# ESP32-Proto2-Layout-D1.net
KiCad netlist of a schematic drawn in EAGLE
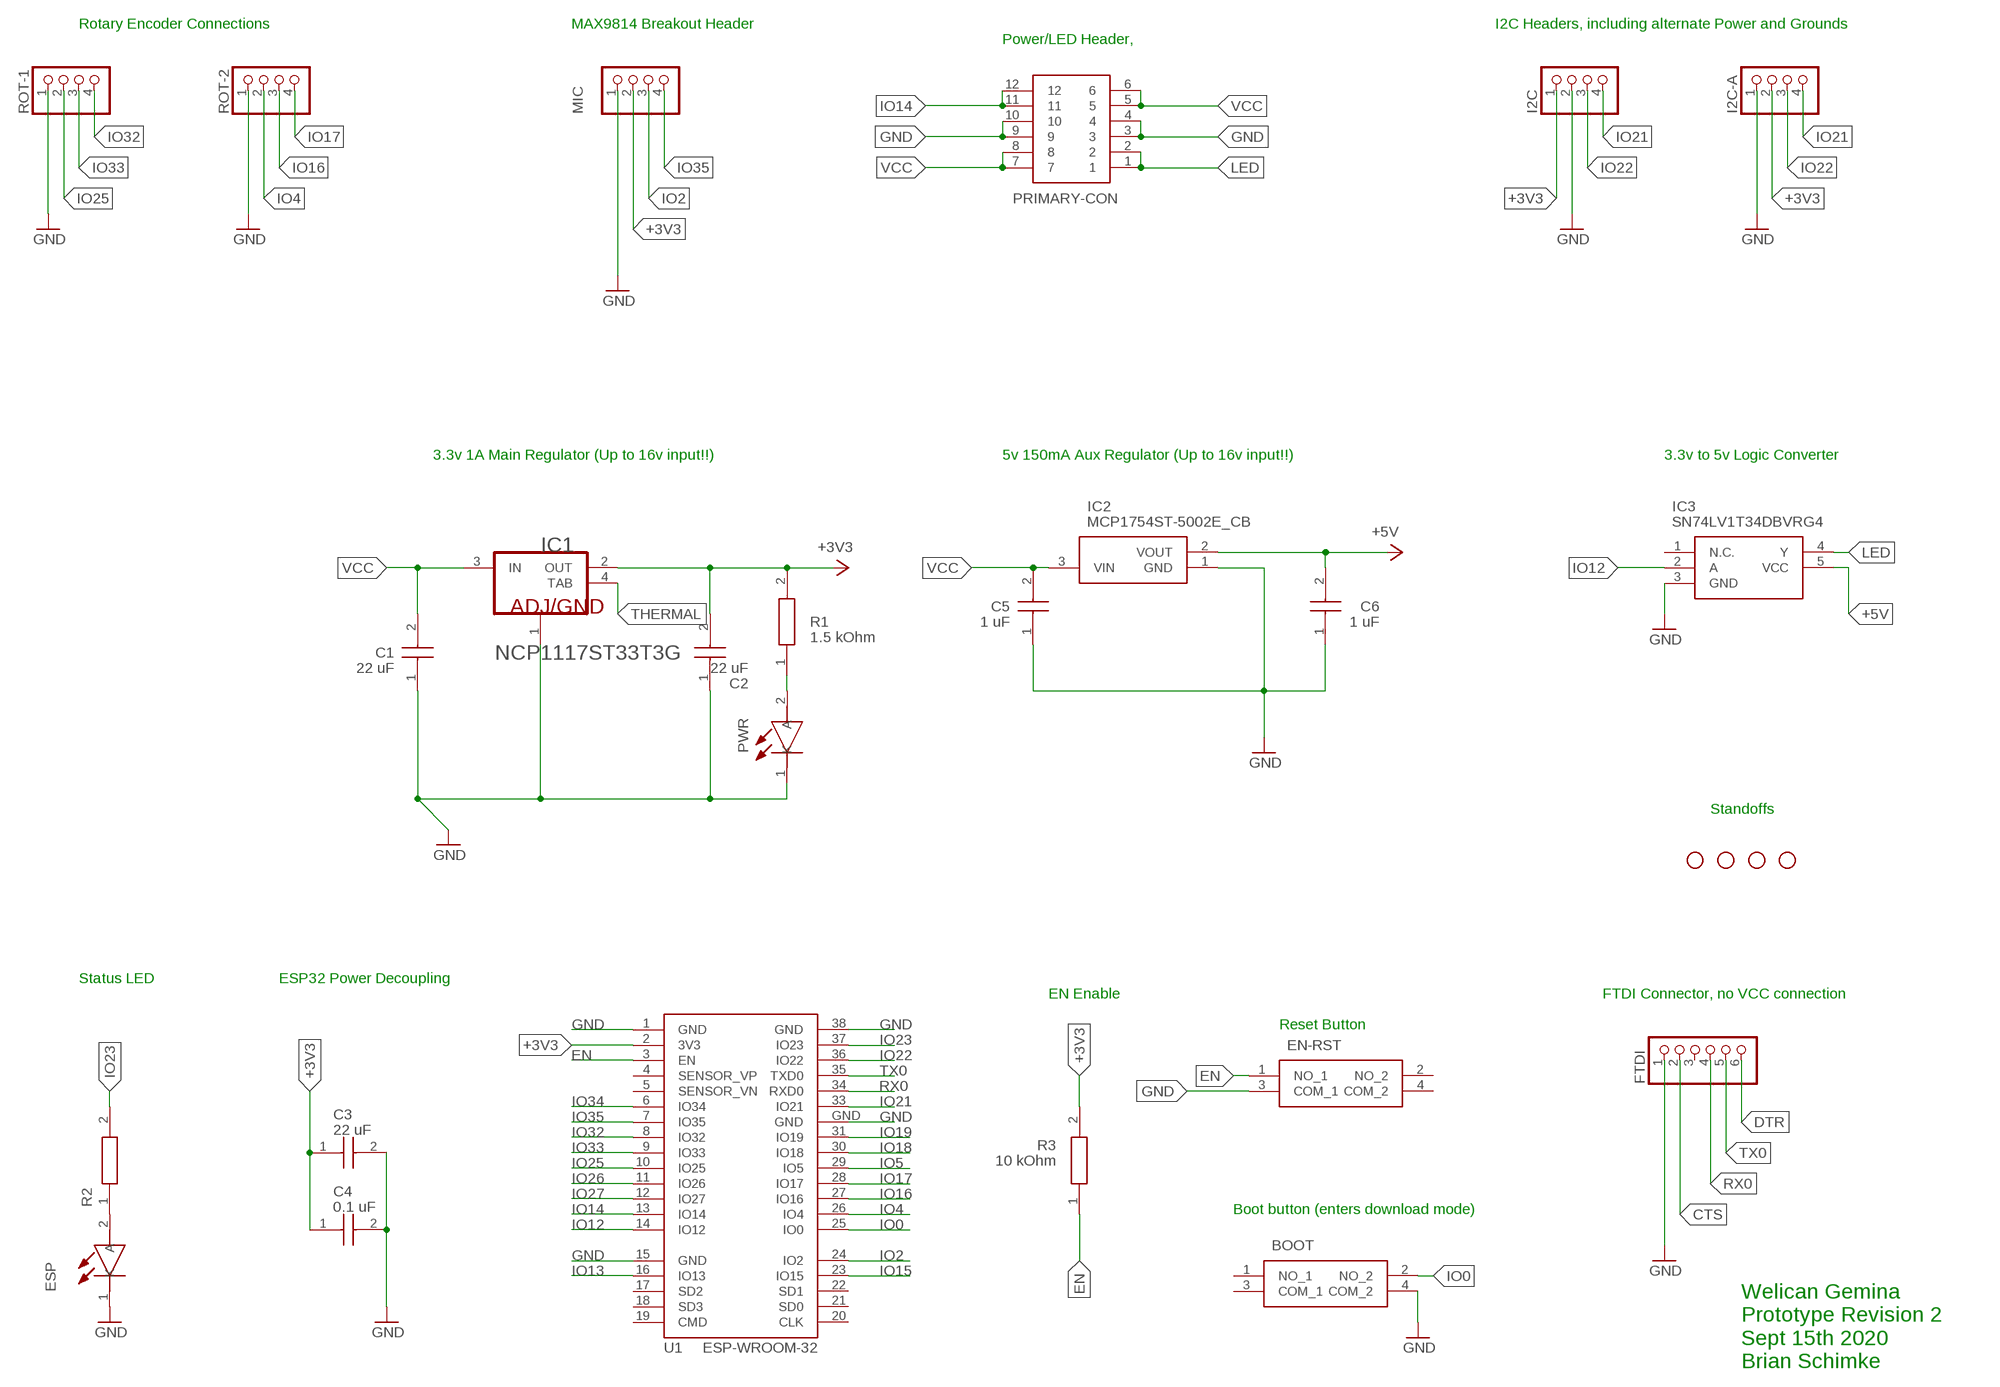
[diagram p0: schematic, sheet 1]

(export (version "E")
  (design (tool "Eeschema 10.0.6"))
  (components
    (comp (ref "BOOT")
      (value "PTS647SK70SMTR2LFS")
      (footprint "eagle-import:PTS647SK70SMTR2LFS")
      (fields (field (name "MOUSER_PART_NUMBER") "611-PTS647SK70SMTR2L"))
      (libsource (lib "eagle-import") (part "PTS647SK70SMTR2LFS"))
    )
    (comp (ref "C1")
      (value "22 uF")
      (footprint "eagle-import:CAPC3216X180N")
      (fields
        (field (name "MANUFACTURER_PART_NUMBER") "C1206C226M4PACTU")
        (field (name "MOUSER_PART_NUMBER") "80-C1206C226M4P")
      )
      (libsource (lib "eagle-import") (part "C1206C226M4PACTU"))
    )
    (comp (ref "C2")
      (value "22 uF")
      (footprint "eagle-import:CAPC3216X180N")
      (fields
        (field (name "MANUFACTURER_PART_NUMBER") "C1206C226M4PACTU")
        (field (name "MOUSER_PART_NUMBER") "80-C1206C226M4P")
      )
      (libsource (lib "eagle-import") (part "C1206C226M4PACTU"))
    )
    (comp (ref "C3")
      (value "22 uF")
      (footprint "eagle-import:CAPC3216X180N")
      (fields
        (field (name "MANUFACTURER_PART_NUMBER") "C1206C226M4PACTU")
        (field (name "MOUSER_PART_NUMBER") "80-C1206C226M4P")
      )
      (libsource (lib "eagle-import") (part "C1206C226M4PACTU"))
    )
    (comp (ref "C4")
      (value "0.1 uF")
      (footprint "eagle-import:CAPC3216X180N")
      (fields
        (field (name "MANUFACTURER_PART_NUMBER") "C1206C226M4PACTU")
        (field (name "MOUSER_PART_NUMBER") "80-C1206C226M4P")
      )
      (libsource (lib "eagle-import") (part "C1206C226M4PACTU"))
    )
    (comp (ref "C5")
      (value "1 uF")
      (footprint "eagle-import:CAPC3216X180N")
      (fields
        (field (name "MANUFACTURER_PART_NUMBER") "C1206C226M4PACTU")
        (field (name "MOUSER_PART_NUMBER") "80-C1206C226M4P")
      )
      (libsource (lib "eagle-import") (part "C1206C226M4PACTU"))
    )
    (comp (ref "C6")
      (value "1 uF")
      (footprint "eagle-import:CAPC3216X180N")
      (fields
        (field (name "MANUFACTURER_PART_NUMBER") "C1206C226M4PACTU")
        (field (name "MOUSER_PART_NUMBER") "80-C1206C226M4P")
      )
      (libsource (lib "eagle-import") (part "C1206C226M4PACTU"))
    )
    (comp (ref "EN-RST")
      (value "PTS647SK70SMTR2LFS")
      (footprint "eagle-import:PTS647SK70SMTR2LFS")
      (fields (field (name "MOUSER_PART_NUMBER") "611-PTS647SK70SMTR2L"))
      (libsource (lib "eagle-import") (part "PTS647SK70SMTR2LFS"))
    )
    (comp (ref "ESP")
      (value "150120AS75000")
      (footprint "eagle-import:LEDSC320X160X78-2N")
      (fields (field (name "MOUSER_PART_NUMBER") "710-150120AS75000"))
      (libsource (lib "eagle-import") (part "150120AS75000"))
    )
    (comp (ref "FTDI")
      (value "PINHD-1X6")
      (footprint "eagle-import:1X06")
      (libsource (lib "eagle-import") (part "PINHD-1X6"))
    )
    (comp (ref "H1")
      (value "STAND-OFF")
      (footprint "eagle-import:STAND-OFF")
      (libsource (lib "eagle-import") (part "STAND-OFF"))
    )
    (comp (ref "H2")
      (value "STAND-OFF")
      (footprint "eagle-import:STAND-OFF")
      (libsource (lib "eagle-import") (part "STAND-OFF"))
    )
    (comp (ref "H3")
      (value "STAND-OFF")
      (footprint "eagle-import:STAND-OFF")
      (libsource (lib "eagle-import") (part "STAND-OFF"))
    )
    (comp (ref "H4")
      (value "STAND-OFF")
      (footprint "eagle-import:STAND-OFF")
      (libsource (lib "eagle-import") (part "STAND-OFF"))
    )
    (comp (ref "I2C")
      (value "PINHD-1X4")
      (footprint "eagle-import:1X04")
      (libsource (lib "eagle-import") (part "PINHD-1X4"))
    )
    (comp (ref "I2C-A")
      (value "PINHD-1X4")
      (footprint "eagle-import:1X04")
      (libsource (lib "eagle-import") (part "PINHD-1X4"))
    )
    (comp (ref "IC1")
      (value "ON_SEMICONDUCTOR_NCP1117ST33T3GON_SEMICONDUCTOR_NCP1117ST33T3G_0_0")
      (footprint "eagle-import:ON_SEMICONDUCTOR_NCP1117ST33T3G_0")
      (fields
        (field (name "MF") "ON Semiconductor")
        (field (name "MPN") "NCP1117ST33T3G")
        (field (name "TOLERANCE") "1%")
      )
      (libsource (lib "eagle-import") (part "ON_SEMICONDUCTOR_NCP1117ST33T3GON_SEMICONDUCTOR_NCP1117ST33T3G_0_0"))
    )
    (comp (ref "IC2")
      (value "MCP1754ST-5002E_CB")
      (footprint "eagle-import:SOT95P255X145-3N")
      (fields
        (field (name "MANUFACTURER_PART_NUMBER") "MCP1754ST-5002E/CB")
        (field (name "MOUSER_PART_NUMBER") "579-MCP1754T-5002ECB")
      )
      (libsource (lib "eagle-import") (part "MCP1754ST-5002E_CB"))
    )
    (comp (ref "IC3")
      (value "SN74LV1T34DBVRG4")
      (footprint "eagle-import:SOT95P280X145-5N")
      (fields (field (name "MOUSER_PART_NUMBER") "595-SN74LV1T34DBVRG4"))
      (libsource (lib "eagle-import") (part "SN74LV1T34DBVRG4"))
    )
    (comp (ref "MIC")
      (value "PINHD-1X4")
      (footprint "eagle-import:1X04")
      (libsource (lib "eagle-import") (part "PINHD-1X4"))
    )
    (comp (ref "PRIMARY-CON")
      (value "1-2834015-6")
      (footprint "eagle-import:SHDR12W90P508X254_2X6_1824X128")
      (fields (field (name "MOUSER_PART_NUMBER") "571-1-2834015-6"))
      (libsource (lib "eagle-import") (part "1-2834015-6"))
    )
    (comp (ref "PWR")
      (value "150120AS75000")
      (footprint "eagle-import:LEDSC320X160X78-2N")
      (fields (field (name "MOUSER_PART_NUMBER") "710-150120AS75000"))
      (libsource (lib "eagle-import") (part "150120AS75000"))
    )
    (comp (ref "R1")
      (value "1.5 kOhm")
      (footprint "eagle-import:RESC3216X60N")
      (fields
        (field (name "MANUFACTURER_PART_NUMBER") "CRCW12061K00FKEB")
        (field (name "MOUSER_PART_NUMBER") "71-CRCW12061K00FKEB")
      )
      (libsource (lib "eagle-import") (part "CRCW12061K00FKEB"))
    )
    (comp (ref "R2")
      (value "CRCW12061K00FKEB")
      (footprint "eagle-import:RESC3216X60N")
      (fields (field (name "MOUSER_PART_NUMBER") "71-CRCW12061K00FKEB"))
      (libsource (lib "eagle-import") (part "CRCW12061K00FKEB"))
    )
    (comp (ref "R3")
      (value "10 kOhm")
      (footprint "eagle-import:RESC3216X60N")
      (fields
        (field (name "MANUFACTURER_PART_NUMBER") "CRCW12061K00FKEB")
        (field (name "MOUSER_PART_NUMBER") "71-CRCW12061K00FKEB")
      )
      (libsource (lib "eagle-import") (part "CRCW12061K00FKEB"))
    )
    (comp (ref "ROT-1")
      (value "PINHD-1X4")
      (footprint "eagle-import:1X04")
      (libsource (lib "eagle-import") (part "PINHD-1X4"))
    )
    (comp (ref "ROT-2")
      (value "PINHD-1X4")
      (footprint "eagle-import:1X04")
      (libsource (lib "eagle-import") (part "PINHD-1X4"))
    )
    (comp (ref "U1")
      (value "ESP-WROOM-32")
      (footprint "eagle-import:ESP-WROOM-32")
      (libsource (lib "eagle-import") (part "ESP-WROOM-32"))
    )
  )
  (nets
    (net (code "1") (name "+3V3") (class "Default")
      (node (ref "C2") (pin "2") (pinfunction "2_2") (pintype "bidirectional"))
      (node (ref "C3") (pin "1") (pinfunction "1_1") (pintype "bidirectional"))
      (node (ref "C4") (pin "1") (pinfunction "1_1") (pintype "bidirectional"))
      (node (ref "I2C") (pin "1") (pinfunction "1_1") (pintype "passive"))
      (node (ref "I2C-A") (pin "2") (pinfunction "2_2") (pintype "passive"))
      (node (ref "IC1") (pin "2") (pinfunction "OUT_2") (pintype "power_in"))
      (node (ref "MIC") (pin "2") (pinfunction "2_2") (pintype "passive"))
      (node (ref "R1") (pin "2") (pinfunction "2_2") (pintype "bidirectional"))
      (node (ref "R3") (pin "2") (pinfunction "2_2") (pintype "bidirectional"))
      (node (ref "U1") (pin "2") (pinfunction "3V3_2") (pintype "power_in"))
    )
    (net (code "2") (name "+5V") (class "Default")
      (node (ref "C6") (pin "2") (pinfunction "2_2") (pintype "bidirectional"))
      (node (ref "IC2") (pin "2") (pinfunction "VOUT_2") (pintype "bidirectional"))
      (node (ref "IC3") (pin "5") (pinfunction "VCC_5") (pintype "bidirectional"))
    )
    (net (code "3") (name "/IO5") (class "Default")
      (node (ref "U1") (pin "29") (pinfunction "IO5_29") (pintype "bidirectional"))
    )
    (net (code "4") (name "/IO13") (class "Default")
      (node (ref "U1") (pin "16") (pinfunction "IO13_16") (pintype "bidirectional"))
    )
    (net (code "5") (name "/IO15") (class "Default")
      (node (ref "U1") (pin "23") (pinfunction "IO15_23") (pintype "bidirectional"))
    )
    (net (code "6") (name "/IO18") (class "Default")
      (node (ref "U1") (pin "30") (pinfunction "IO18_30") (pintype "bidirectional"))
    )
    (net (code "7") (name "/IO19") (class "Default")
      (node (ref "U1") (pin "31") (pinfunction "IO19_31") (pintype "bidirectional"))
    )
    (net (code "8") (name "/IO26") (class "Default")
      (node (ref "U1") (pin "11") (pinfunction "IO26_11") (pintype "bidirectional"))
    )
    (net (code "9") (name "/IO27") (class "Default")
      (node (ref "U1") (pin "12") (pinfunction "IO27_12") (pintype "bidirectional"))
    )
    (net (code "10") (name "/IO34") (class "Default")
      (node (ref "U1") (pin "6") (pinfunction "IO34_6") (pintype "bidirectional"))
    )
    (net (code "11") (name "CTS") (class "Default")
      (node (ref "FTDI") (pin "2") (pinfunction "2_2") (pintype "passive"))
    )
    (net (code "12") (name "DTR") (class "Default")
      (node (ref "FTDI") (pin "6") (pinfunction "6_6") (pintype "passive"))
    )
    (net (code "13") (name "EN") (class "Default")
      (node (ref "EN-RST") (pin "1") (pinfunction "NO_1_1") (pintype "bidirectional"))
      (node (ref "R3") (pin "1") (pinfunction "1_1") (pintype "bidirectional"))
      (node (ref "U1") (pin "3") (pinfunction "EN_3") (pintype "input"))
    )
    (net (code "14") (name "GND") (class "Default")
      (node (ref "BOOT") (pin "4") (pinfunction "COM_2_4") (pintype "bidirectional"))
      (node (ref "C1") (pin "1") (pinfunction "1_1") (pintype "bidirectional"))
      (node (ref "C2") (pin "1") (pinfunction "1_1") (pintype "bidirectional"))
      (node (ref "C3") (pin "2") (pinfunction "2_2") (pintype "bidirectional"))
      (node (ref "C4") (pin "2") (pinfunction "2_2") (pintype "bidirectional"))
      (node (ref "C5") (pin "1") (pinfunction "1_1") (pintype "bidirectional"))
      (node (ref "C6") (pin "1") (pinfunction "1_1") (pintype "bidirectional"))
      (node (ref "EN-RST") (pin "3") (pinfunction "COM_1_3") (pintype "bidirectional"))
      (node (ref "ESP") (pin "1") (pinfunction "K_1") (pintype "bidirectional"))
      (node (ref "FTDI") (pin "1") (pinfunction "1_1") (pintype "passive"))
      (node (ref "I2C") (pin "2") (pinfunction "2_2") (pintype "passive"))
      (node (ref "I2C-A") (pin "1") (pinfunction "1_1") (pintype "passive"))
      (node (ref "IC1") (pin "1") (pinfunction "ADJ/GND_1") (pintype "passive"))
      (node (ref "IC2") (pin "1") (pinfunction "GND_1") (pintype "bidirectional"))
      (node (ref "IC3") (pin "3") (pinfunction "GND_3") (pintype "bidirectional"))
      (node (ref "MIC") (pin "1") (pinfunction "1_1") (pintype "passive"))
      (node (ref "PRIMARY-CON") (pin "10") (pinfunction "10_10") (pintype "bidirectional"))
      (node (ref "PRIMARY-CON") (pin "3") (pinfunction "3_3") (pintype "bidirectional"))
      (node (ref "PRIMARY-CON") (pin "4") (pinfunction "4_4") (pintype "bidirectional"))
      (node (ref "PRIMARY-CON") (pin "9") (pinfunction "9_9") (pintype "bidirectional"))
      (node (ref "PWR") (pin "1") (pinfunction "K_1") (pintype "bidirectional"))
      (node (ref "ROT-1") (pin "1") (pinfunction "1_1") (pintype "passive"))
      (node (ref "ROT-2") (pin "1") (pinfunction "1_1") (pintype "passive"))
      (node (ref "U1") (pin "1") (pinfunction "GND_1") (pintype "power_in"))
      (node (ref "U1") (pin "15") (pinfunction "GND_15") (pintype "power_in"))
      (node (ref "U1") (pin "38") (pinfunction "GND_38") (pintype "power_in"))
      (node (ref "U1") (pin "GND") (pinfunction "GND_GND") (pintype "power_in"))
    )
    (net (code "15") (name "IO0") (class "Default")
      (node (ref "BOOT") (pin "2") (pinfunction "NO_2_2") (pintype "bidirectional"))
      (node (ref "U1") (pin "25") (pinfunction "IO0_25") (pintype "bidirectional"))
    )
    (net (code "16") (name "IO2") (class "Default")
      (node (ref "MIC") (pin "3") (pinfunction "3_3") (pintype "passive"))
      (node (ref "U1") (pin "24") (pinfunction "IO2_24") (pintype "bidirectional"))
    )
    (net (code "17") (name "IO4") (class "Default")
      (node (ref "ROT-2") (pin "2") (pinfunction "2_2") (pintype "passive"))
      (node (ref "U1") (pin "26") (pinfunction "IO4_26") (pintype "bidirectional"))
    )
    (net (code "18") (name "IO12") (class "Default")
      (node (ref "IC3") (pin "2") (pinfunction "A_2") (pintype "bidirectional"))
      (node (ref "U1") (pin "14") (pinfunction "IO12_14") (pintype "bidirectional"))
    )
    (net (code "19") (name "IO14") (class "Default")
      (node (ref "PRIMARY-CON") (pin "11") (pinfunction "11_11") (pintype "bidirectional"))
      (node (ref "PRIMARY-CON") (pin "12") (pinfunction "12_12") (pintype "bidirectional"))
      (node (ref "U1") (pin "13") (pinfunction "IO14_13") (pintype "bidirectional"))
    )
    (net (code "20") (name "IO16") (class "Default")
      (node (ref "ROT-2") (pin "3") (pinfunction "3_3") (pintype "passive"))
      (node (ref "U1") (pin "27") (pinfunction "IO16_27") (pintype "bidirectional"))
    )
    (net (code "21") (name "IO17") (class "Default")
      (node (ref "ROT-2") (pin "4") (pinfunction "4_4") (pintype "passive"))
      (node (ref "U1") (pin "28") (pinfunction "IO17_28") (pintype "bidirectional"))
    )
    (net (code "22") (name "IO21") (class "Default")
      (node (ref "I2C") (pin "4") (pinfunction "4_4") (pintype "passive"))
      (node (ref "I2C-A") (pin "4") (pinfunction "4_4") (pintype "passive"))
      (node (ref "U1") (pin "33") (pinfunction "IO21_33") (pintype "bidirectional"))
    )
    (net (code "23") (name "IO22") (class "Default")
      (node (ref "I2C") (pin "3") (pinfunction "3_3") (pintype "passive"))
      (node (ref "I2C-A") (pin "3") (pinfunction "3_3") (pintype "passive"))
      (node (ref "U1") (pin "36") (pinfunction "IO22_36") (pintype "bidirectional"))
    )
    (net (code "24") (name "IO23") (class "Default")
      (node (ref "R2") (pin "2") (pinfunction "2_2") (pintype "bidirectional"))
      (node (ref "U1") (pin "37") (pinfunction "IO23_37") (pintype "bidirectional"))
    )
    (net (code "25") (name "IO25") (class "Default")
      (node (ref "ROT-1") (pin "2") (pinfunction "2_2") (pintype "passive"))
      (node (ref "U1") (pin "10") (pinfunction "IO25_10") (pintype "bidirectional"))
    )
    (net (code "26") (name "IO32") (class "Default")
      (node (ref "ROT-1") (pin "4") (pinfunction "4_4") (pintype "passive"))
      (node (ref "U1") (pin "8") (pinfunction "IO32_8") (pintype "bidirectional"))
    )
    (net (code "27") (name "IO33") (class "Default")
      (node (ref "ROT-1") (pin "3") (pinfunction "3_3") (pintype "passive"))
      (node (ref "U1") (pin "9") (pinfunction "IO33_9") (pintype "bidirectional"))
    )
    (net (code "28") (name "IO35") (class "Default")
      (node (ref "MIC") (pin "4") (pinfunction "4_4") (pintype "passive"))
      (node (ref "U1") (pin "7") (pinfunction "IO35_7") (pintype "bidirectional"))
    )
    (net (code "29") (name "LED") (class "Default")
      (node (ref "IC3") (pin "4") (pinfunction "Y_4") (pintype "bidirectional"))
      (node (ref "PRIMARY-CON") (pin "1") (pinfunction "1_1") (pintype "bidirectional"))
      (node (ref "PRIMARY-CON") (pin "2") (pinfunction "2_2") (pintype "bidirectional"))
    )
    (net (code "30") (name "Net-(ESP-A)") (class "Default")
      (node (ref "ESP") (pin "2") (pinfunction "A_2") (pintype "bidirectional"))
      (node (ref "R2") (pin "1") (pinfunction "1_1") (pintype "bidirectional"))
    )
    (net (code "31") (name "Net-(PWR-A)") (class "Default")
      (node (ref "PWR") (pin "2") (pinfunction "A_2") (pintype "bidirectional"))
      (node (ref "R1") (pin "1") (pinfunction "1_1") (pintype "bidirectional"))
    )
    (net (code "32") (name "RX0") (class "Default")
      (node (ref "FTDI") (pin "4") (pinfunction "4_4") (pintype "passive"))
      (node (ref "U1") (pin "34") (pinfunction "RXD0_34") (pintype "bidirectional"))
    )
    (net (code "33") (name "THERMAL") (class "Default")
      (node (ref "IC1") (pin "4") (pinfunction "TAB_4") (pintype "passive"))
    )
    (net (code "34") (name "TX0") (class "Default")
      (node (ref "FTDI") (pin "5") (pinfunction "5_5") (pintype "passive"))
      (node (ref "U1") (pin "35") (pinfunction "TXD0_35") (pintype "bidirectional"))
    )
    (net (code "35") (name "VCC") (class "Default")
      (node (ref "C1") (pin "2") (pinfunction "2_2") (pintype "bidirectional"))
      (node (ref "C5") (pin "2") (pinfunction "2_2") (pintype "bidirectional"))
      (node (ref "IC1") (pin "3") (pinfunction "IN_3") (pintype "power_in"))
      (node (ref "IC2") (pin "3") (pinfunction "VIN_3") (pintype "bidirectional"))
      (node (ref "PRIMARY-CON") (pin "5") (pinfunction "5_5") (pintype "bidirectional"))
      (node (ref "PRIMARY-CON") (pin "6") (pinfunction "6_6") (pintype "bidirectional"))
      (node (ref "PRIMARY-CON") (pin "7") (pinfunction "7_7") (pintype "bidirectional"))
      (node (ref "PRIMARY-CON") (pin "8") (pinfunction "8_8") (pintype "bidirectional"))
    )
    (net (code "36") (name "unconnected-(BOOT-COM_1-Pad3)") (class "Default")
      (node (ref "BOOT") (pin "3") (pinfunction "COM_1_3") (pintype "bidirectional"))
    )
    (net (code "37") (name "unconnected-(BOOT-NO_1-Pad1)") (class "Default")
      (node (ref "BOOT") (pin "1") (pinfunction "NO_1_1") (pintype "bidirectional"))
    )
    (net (code "38") (name "unconnected-(EN-RST-COM_2-Pad4)") (class "Default")
      (node (ref "EN-RST") (pin "4") (pinfunction "COM_2_4") (pintype "bidirectional"))
    )
    (net (code "39") (name "unconnected-(EN-RST-NO_2-Pad2)") (class "Default")
      (node (ref "EN-RST") (pin "2") (pinfunction "NO_2_2") (pintype "bidirectional"))
    )
    (net (code "40") (name "unconnected-(FTDI-Pad3)") (class "Default")
      (node (ref "FTDI") (pin "3") (pinfunction "3_3") (pintype "passive"))
    )
    (net (code "41") (name "unconnected-(IC3-N.C.-Pad1)") (class "Default")
      (node (ref "IC3") (pin "1") (pinfunction "N.C._1") (pintype "no_connect"))
    )
    (net (code "42") (name "unconnected-(U1-CLK-Pad20)") (class "Default")
      (node (ref "U1") (pin "20") (pinfunction "CLK_20") (pintype "bidirectional"))
    )
    (net (code "43") (name "unconnected-(U1-CMD-Pad19)") (class "Default")
      (node (ref "U1") (pin "19") (pinfunction "CMD_19") (pintype "bidirectional"))
    )
    (net (code "44") (name "unconnected-(U1-SD0-Pad21)") (class "Default")
      (node (ref "U1") (pin "21") (pinfunction "SD0_21") (pintype "bidirectional"))
    )
    (net (code "45") (name "unconnected-(U1-SD1-Pad22)") (class "Default")
      (node (ref "U1") (pin "22") (pinfunction "SD1_22") (pintype "bidirectional"))
    )
    (net (code "46") (name "unconnected-(U1-SD2-Pad17)") (class "Default")
      (node (ref "U1") (pin "17") (pinfunction "SD2_17") (pintype "bidirectional"))
    )
    (net (code "47") (name "unconnected-(U1-SD3-Pad18)") (class "Default")
      (node (ref "U1") (pin "18") (pinfunction "SD3_18") (pintype "bidirectional"))
    )
    (net (code "48") (name "unconnected-(U1-SENSOR_VN-Pad5)") (class "Default")
      (node (ref "U1") (pin "5") (pinfunction "SENSOR_VN_5") (pintype "bidirectional"))
    )
    (net (code "49") (name "unconnected-(U1-SENSOR_VP-Pad4)") (class "Default")
      (node (ref "U1") (pin "4") (pinfunction "SENSOR_VP_4") (pintype "bidirectional"))
    )
  )
)
